# DebuggerMCU.net
KiCad netlist of a schematic drawn in Altium Designer
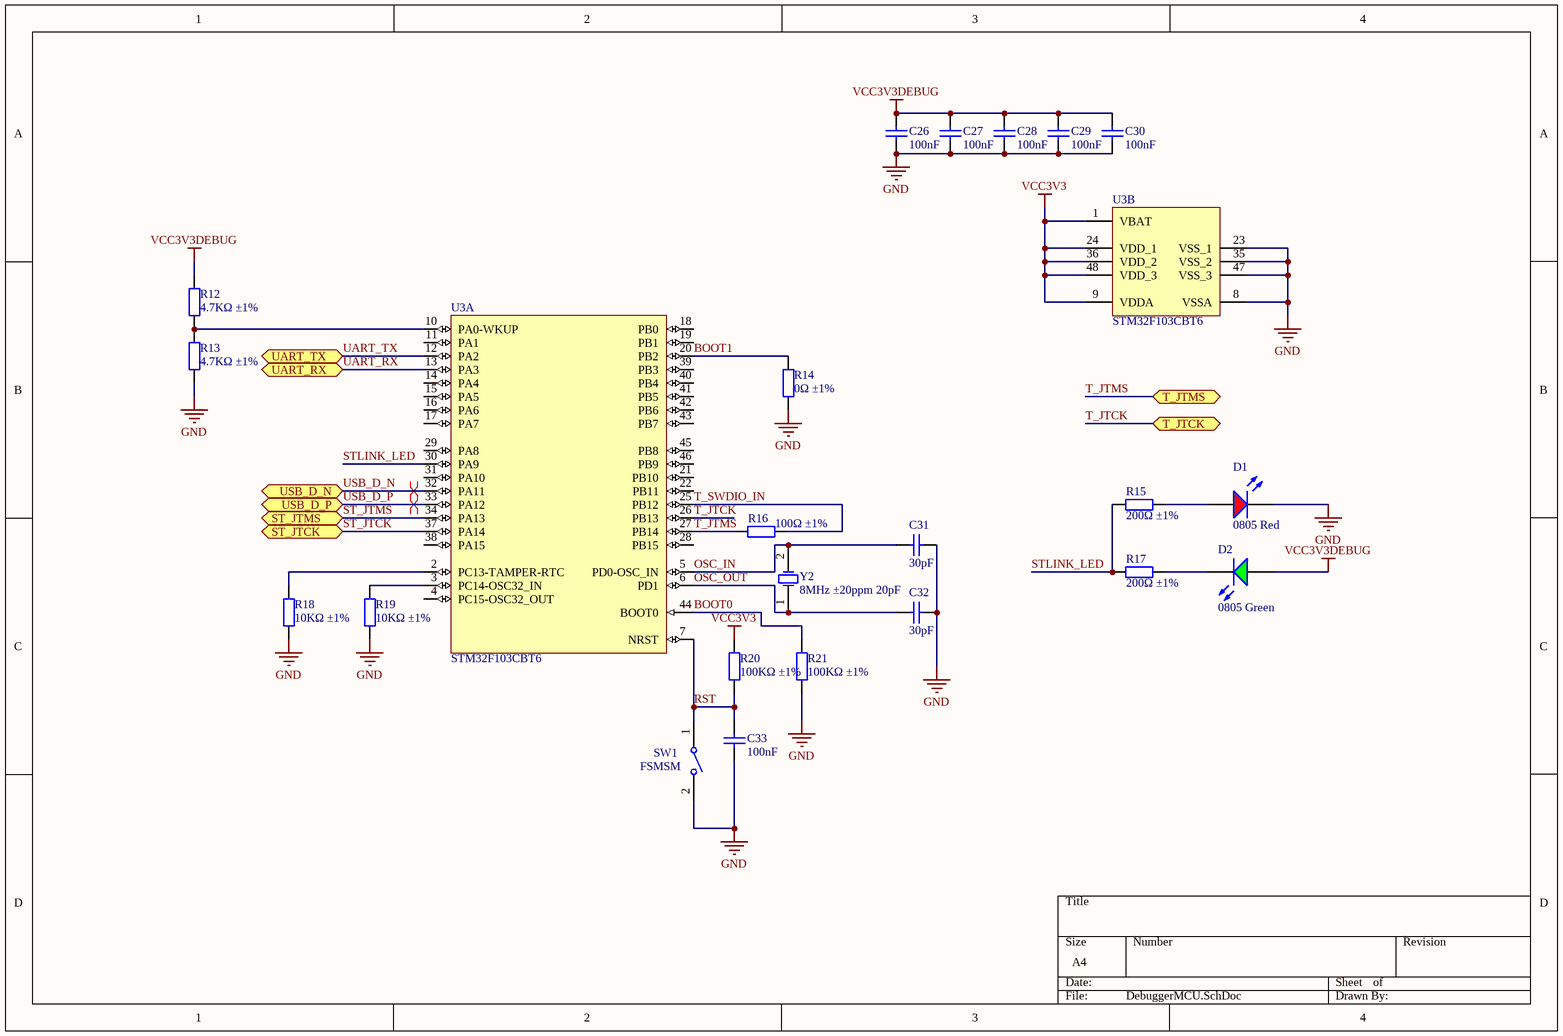
[diagram p0: DebuggerMCU.SchDoc]

(export (version "E")
  (design (tool "Eeschema 10.0.6"))
  (components
    (comp (ref "C26")
      (value "100nF")
      (footprint "0402_C")
      (description "Chip capacitors")
      (fields
        (field (name "MANUFACTURER") "Samsung Electro-Mechanics")
        (field (name "PARTNUMBER") "CL05B104KO5NNNC")
      )
      (libsource (lib "Miscellaneous Devices LC") (part "0402 100nF (104) 10% 16V"))
    )
    (comp (ref "C27")
      (value "100nF")
      (footprint "0402_C")
      (description "Chip capacitors")
      (fields
        (field (name "MANUFACTURER") "Samsung Electro-Mechanics")
        (field (name "PARTNUMBER") "CL05B104KO5NNNC")
      )
      (libsource (lib "Miscellaneous Devices LC") (part "0402 100nF (104) 10% 16V"))
    )
    (comp (ref "C28")
      (value "100nF")
      (footprint "0402_C")
      (description "Chip capacitors")
      (fields
        (field (name "MANUFACTURER") "Samsung Electro-Mechanics")
        (field (name "PARTNUMBER") "CL05B104KO5NNNC")
      )
      (libsource (lib "Miscellaneous Devices LC") (part "0402 100nF (104) 10% 16V"))
    )
    (comp (ref "C29")
      (value "100nF")
      (footprint "0402_C")
      (description "Chip capacitors")
      (fields
        (field (name "MANUFACTURER") "Samsung Electro-Mechanics")
        (field (name "PARTNUMBER") "CL05B104KO5NNNC")
      )
      (libsource (lib "Miscellaneous Devices LC") (part "0402 100nF (104) 10% 16V"))
    )
    (comp (ref "C30")
      (value "100nF")
      (footprint "0402_C")
      (description "Chip capacitors")
      (fields
        (field (name "MANUFACTURER") "Samsung Electro-Mechanics")
        (field (name "PARTNUMBER") "CL05B104KO5NNNC")
      )
      (libsource (lib "Miscellaneous Devices LC") (part "0402 100nF (104) 10% 16V"))
    )
    (comp (ref "C31")
      (value "30pF")
      (footprint "0402_C")
      (description "Chip capacitors")
      (fields
        (field (name "MANUFACTURER") "Guangdong Fenghua Advanced Tech")
        (field (name "PARTNUMBER") "0402CG300J500NT")
      )
      (libsource (lib "Miscellaneous Devices LC") (part "0402 30pF (300) 5% 50V"))
    )
    (comp (ref "C32")
      (value "30pF")
      (footprint "0402_C")
      (description "Chip capacitors")
      (fields
        (field (name "MANUFACTURER") "Guangdong Fenghua Advanced Tech")
        (field (name "PARTNUMBER") "0402CG300J500NT")
      )
      (libsource (lib "Miscellaneous Devices LC") (part "0402 30pF (300) 5% 50V"))
    )
    (comp (ref "C33")
      (value "100nF")
      (footprint "0402_C")
      (description "Chip capacitors")
      (fields
        (field (name "MANUFACTURER") "Samsung Electro-Mechanics")
        (field (name "PARTNUMBER") "CL05B104KO5NNNC")
      )
      (libsource (lib "Miscellaneous Devices LC") (part "0402 100nF (104) 10% 16V"))
    )
    (comp (ref "D1")
      (value "0805 Red")
      (footprint "0805_LED_S1")
      (description "LED")
      (libsource (lib "Miscellaneous Devices LC") (part "0805 LED Red"))
    )
    (comp (ref "D2")
      (value "0805 Green")
      (footprint "0805_LED_S1")
      (description "LED")
      (libsource (lib "Miscellaneous Devices LC") (part "0805 LED Green"))
    )
    (comp (ref "R12")
      (value "4.7KΩ ±1%")
      (footprint "0805_R")
      (description "Chip resistor")
      (fields (field (name "MANUFACTURER") "Uniroyal Elec") (field (name "POWER") "1/8W"))
      (libsource (lib "Miscellaneous Devices LC") (part "0805 4.7K (4701) 1%"))
    )
    (comp (ref "R13")
      (value "4.7KΩ ±1%")
      (footprint "0805_R")
      (description "Chip resistor")
      (fields (field (name "MANUFACTURER") "Uniroyal Elec") (field (name "POWER") "1/8W"))
      (libsource (lib "Miscellaneous Devices LC") (part "0805 4.7K (4701) 1%"))
    )
    (comp (ref "R14")
      (value "0Ω ±1%")
      (footprint "0402_R")
      (description "Chip resistor")
      (fields (field (name "POWER") "1/16W") (field (name "MANUFACTURER") "Uniroyal Elec"))
      (libsource (lib "Miscellaneous Devices LC") (part "0402 0R (0R0) 1%"))
    )
    (comp (ref "R15")
      (value "200Ω ±1%")
      (footprint "0402_R")
      (description "Chip resistor")
      (fields (field (name "MANUFACTURER") "Uniroyal Elec") (field (name "PARTNUMBER") "0402WGF2000TCE"))
      (libsource (lib "Miscellaneous Devices LC") (part "0402 200R (2000) 1%"))
    )
    (comp (ref "R16")
      (value "100Ω ±1%")
      (footprint "0402_R")
      (description "Chip resistor")
      (fields (field (name "MANUFACTURER") "Uniroyal Elec") (field (name "PARTNUMBER") "0402WGF1000TCE"))
      (libsource (lib "Miscellaneous Devices LC") (part "0402 100R (1000) 1%"))
    )
    (comp (ref "R17")
      (value "200Ω ±1%")
      (footprint "0402_R")
      (description "Chip resistor")
      (fields (field (name "MANUFACTURER") "Uniroyal Elec") (field (name "PARTNUMBER") "0402WGF2000TCE"))
      (libsource (lib "Miscellaneous Devices LC") (part "0402 200R (2000) 1%"))
    )
    (comp (ref "R18")
      (value "10KΩ ±1%")
      (footprint "0402_R")
      (description "Chip resistor")
      (fields (field (name "MANUFACTURER") "Uniroyal Elec") (field (name "PARTNUMBER") "0402WGF1002TCE"))
      (libsource (lib "Miscellaneous Devices LC") (part "0402 10K (1002) 1%"))
    )
    (comp (ref "R19")
      (value "10KΩ ±1%")
      (footprint "0402_R")
      (description "Chip resistor")
      (fields (field (name "MANUFACTURER") "Uniroyal Elec") (field (name "PARTNUMBER") "0402WGF1002TCE"))
      (libsource (lib "Miscellaneous Devices LC") (part "0402 10K (1002) 1%"))
    )
    (comp (ref "R20")
      (value "100KΩ ±1%")
      (footprint "0402_R")
      (description "Chip resistor")
      (fields (field (name "MANUFACTURER") "Uniroyal Elec") (field (name "PARTNUMBER") "0402WGF1003TCE"))
      (libsource (lib "Miscellaneous Devices LC") (part "0402 100K (1003) 1%"))
    )
    (comp (ref "R21")
      (value "100KΩ ±1%")
      (footprint "0402_R")
      (description "Chip resistor")
      (fields (field (name "MANUFACTURER") "Uniroyal Elec") (field (name "PARTNUMBER") "0402WGF1003TCE"))
      (libsource (lib "Miscellaneous Devices LC") (part "0402 100K (1003) 1%"))
    )
    (comp (ref "SW1")
      (value "FSMSM")
      (footprint "TECO-FSMSM-2_V")
      (description "FSMSM Push Button Switch, 50 mA, -35 to 85 degC, 2-Pin SMD, RoHS, Bulk")
      (fields (field (name "MANUFACTURER") "TE Connectivity"))
      (libsource (lib "Altium Content Vault") (part "SW-SPST-2_C"))
    )
    (comp (ref "U3")
      (value "STM32F103CBT6")
      (footprint "LQFP-48_7x7x05P")
      (description "ARM")
      (libsource (lib "Miscellaneous Devices LC") (part "STM32F103CBT6"))
    )
    (comp (ref "Y2")
      (value "8MHz ±20ppm 20pF")
      (footprint "SMD-5032_2P")
      (description "贴片晶振")
      (libsource (lib "Miscellaneous Devices LC") (part "SMD-5032_2P 8MHz 20ppm 20pF"))
    )
  )
  (nets
    (net (code "1") (name "/BOOT0") (class "Default")
      (node (ref "R21") (pin "2") (pinfunction "2_2") (pintype "passive"))
      (node (ref "U3") (pin "44") (pinfunction "BOOT0_44") (pintype "input"))
    )
    (net (code "2") (name "/BOOT1") (class "Default")
      (node (ref "R14") (pin "2") (pinfunction "2_2") (pintype "passive"))
      (node (ref "U3") (pin "20") (pinfunction "PB2_20") (pintype "bidirectional"))
    )
    (net (code "3") (name "/OSC_IN") (class "Default")
      (node (ref "C31") (pin "1") (pinfunction "1_1") (pintype "passive"))
      (node (ref "U3") (pin "5") (pinfunction "PD0-OSC_IN_5") (pintype "bidirectional"))
      (node (ref "Y2") (pin "2") (pinfunction "OSC2_2") (pintype "passive"))
    )
    (net (code "4") (name "/OSC_OUT") (class "Default")
      (node (ref "C32") (pin "1") (pinfunction "1_1") (pintype "passive"))
      (node (ref "U3") (pin "6") (pinfunction "PD1_6") (pintype "bidirectional"))
      (node (ref "Y2") (pin "1") (pinfunction "OSC1_1") (pintype "passive"))
    )
    (net (code "5") (name "/RST") (class "Default")
      (node (ref "C33") (pin "2") (pinfunction "2_2") (pintype "passive"))
      (node (ref "R20") (pin "1") (pinfunction "1_1") (pintype "passive"))
      (node (ref "SW1") (pin "1") (pinfunction "1_1") (pintype "passive"))
      (node (ref "U3") (pin "7") (pinfunction "NRST_7") (pintype "bidirectional"))
    )
    (net (code "6") (name "/STLINK_LED") (class "Default")
      (node (ref "R15") (pin "1") (pinfunction "1_1") (pintype "passive"))
      (node (ref "R17") (pin "1") (pinfunction "1_1") (pintype "passive"))
      (node (ref "U3") (pin "30") (pinfunction "PA9_30") (pintype "bidirectional"))
    )
    (net (code "7") (name "/ST_JTCK") (class "Default")
      (node (ref "U3") (pin "37") (pinfunction "PA14_37") (pintype "bidirectional"))
    )
    (net (code "8") (name "/ST_JTMS") (class "Default")
      (node (ref "U3") (pin "34") (pinfunction "PA13_34") (pintype "bidirectional"))
    )
    (net (code "9") (name "/T_JTCK") (class "Default")
      (node (ref "U3") (pin "26") (pinfunction "PB13_26") (pintype "bidirectional"))
    )
    (net (code "10") (name "/T_JTMS") (class "Default")
      (node (ref "R16") (pin "2") (pinfunction "2_2") (pintype "passive"))
      (node (ref "U3") (pin "27") (pinfunction "PB14_27") (pintype "bidirectional"))
    )
    (net (code "11") (name "/T_SWDIO_IN") (class "Default")
      (node (ref "R16") (pin "1") (pinfunction "1_1") (pintype "passive"))
      (node (ref "U3") (pin "25") (pinfunction "PB12_25") (pintype "bidirectional"))
    )
    (net (code "12") (name "/UART_RX") (class "Default")
      (node (ref "U3") (pin "13") (pinfunction "PA3_13") (pintype "bidirectional"))
    )
    (net (code "13") (name "/UART_TX") (class "Default")
      (node (ref "U3") (pin "12") (pinfunction "PA2_12") (pintype "bidirectional"))
    )
    (net (code "14") (name "/USB_D_N") (class "Default")
      (node (ref "U3") (pin "32") (pinfunction "PA11_32") (pintype "bidirectional"))
    )
    (net (code "15") (name "/USB_D_P") (class "Default")
      (node (ref "U3") (pin "33") (pinfunction "PA12_33") (pintype "bidirectional"))
    )
    (net (code "16") (name "GND") (class "Default")
      (node (ref "C26") (pin "1") (pinfunction "1_1") (pintype "passive"))
      (node (ref "C27") (pin "1") (pinfunction "1_1") (pintype "passive"))
      (node (ref "C28") (pin "1") (pinfunction "1_1") (pintype "passive"))
      (node (ref "C29") (pin "1") (pinfunction "1_1") (pintype "passive"))
      (node (ref "C30") (pin "1") (pinfunction "1_1") (pintype "passive"))
      (node (ref "C31") (pin "2") (pinfunction "2_2") (pintype "passive"))
      (node (ref "C32") (pin "2") (pinfunction "2_2") (pintype "passive"))
      (node (ref "C33") (pin "1") (pinfunction "1_1") (pintype "passive"))
      (node (ref "D1") (pin "K") (pinfunction "K_K") (pintype "passive"))
      (node (ref "R13") (pin "1") (pinfunction "1_1") (pintype "passive"))
      (node (ref "R14") (pin "1") (pinfunction "1_1") (pintype "passive"))
      (node (ref "R18") (pin "1") (pinfunction "1_1") (pintype "passive"))
      (node (ref "R19") (pin "1") (pinfunction "1_1") (pintype "passive"))
      (node (ref "R21") (pin "1") (pinfunction "1_1") (pintype "passive"))
      (node (ref "SW1") (pin "2") (pinfunction "2_2") (pintype "passive"))
      (node (ref "U3") (pin "23") (pinfunction "VSS_1_23") (pintype "power_in"))
      (node (ref "U3") (pin "35") (pinfunction "VSS_2_35") (pintype "power_in"))
      (node (ref "U3") (pin "47") (pinfunction "VSS_3_47") (pintype "power_in"))
      (node (ref "U3") (pin "8") (pinfunction "VSSA_8") (pintype "power_in"))
    )
    (net (code "17") (name "Net-(D1-PadA)") (class "Default")
      (node (ref "D1") (pin "A") (pinfunction "A_A") (pintype "passive"))
      (node (ref "R15") (pin "2") (pinfunction "2_2") (pintype "passive"))
    )
    (net (code "18") (name "Net-(D2-PadK)") (class "Default")
      (node (ref "D2") (pin "K") (pinfunction "K_K") (pintype "passive"))
      (node (ref "R17") (pin "2") (pinfunction "2_2") (pintype "passive"))
    )
    (net (code "19") (name "Net-(U3A-PA0-WKUP)") (class "Default")
      (node (ref "R12") (pin "1") (pinfunction "1_1") (pintype "passive"))
      (node (ref "R13") (pin "2") (pinfunction "2_2") (pintype "passive"))
      (node (ref "U3") (pin "10") (pinfunction "PA0-WKUP_10") (pintype "bidirectional"))
    )
    (net (code "20") (name "Net-(U3A-PC13-TAMPER-RTC)") (class "Default")
      (node (ref "R18") (pin "2") (pinfunction "2_2") (pintype "passive"))
      (node (ref "U3") (pin "2") (pinfunction "PC13-TAMPER-RTC_2") (pintype "bidirectional"))
    )
    (net (code "21") (name "Net-(U3A-PC14-OSC32_IN)") (class "Default")
      (node (ref "R19") (pin "2") (pinfunction "2_2") (pintype "passive"))
      (node (ref "U3") (pin "3") (pinfunction "PC14-OSC32_IN_3") (pintype "bidirectional"))
    )
    (net (code "22") (name "VCC3V3") (class "Default")
      (node (ref "R20") (pin "2") (pinfunction "2_2") (pintype "passive"))
      (node (ref "U3") (pin "1") (pinfunction "VBAT_1") (pintype "power_in"))
      (node (ref "U3") (pin "24") (pinfunction "VDD_1_24") (pintype "power_in"))
      (node (ref "U3") (pin "36") (pinfunction "VDD_2_36") (pintype "power_in"))
      (node (ref "U3") (pin "48") (pinfunction "VDD_3_48") (pintype "power_in"))
      (node (ref "U3") (pin "9") (pinfunction "VDDA_9") (pintype "power_in"))
    )
    (net (code "23") (name "VCC3V3DEBUG") (class "Default")
      (node (ref "C26") (pin "2") (pinfunction "2_2") (pintype "passive"))
      (node (ref "C27") (pin "2") (pinfunction "2_2") (pintype "passive"))
      (node (ref "C28") (pin "2") (pinfunction "2_2") (pintype "passive"))
      (node (ref "C29") (pin "2") (pinfunction "2_2") (pintype "passive"))
      (node (ref "C30") (pin "2") (pinfunction "2_2") (pintype "passive"))
      (node (ref "D2") (pin "A") (pinfunction "A_A") (pintype "passive"))
      (node (ref "R12") (pin "2") (pinfunction "2_2") (pintype "passive"))
    )
    (net (code "24") (name "unconnected-(U3A-PA1-Pad11)") (class "Default")
      (node (ref "U3") (pin "11") (pinfunction "PA1_11") (pintype "bidirectional"))
    )
    (net (code "25") (name "unconnected-(U3A-PA4-Pad14)") (class "Default")
      (node (ref "U3") (pin "14") (pinfunction "PA4_14") (pintype "bidirectional"))
    )
    (net (code "26") (name "unconnected-(U3A-PA5-Pad15)") (class "Default")
      (node (ref "U3") (pin "15") (pinfunction "PA5_15") (pintype "bidirectional"))
    )
    (net (code "27") (name "unconnected-(U3A-PA6-Pad16)") (class "Default")
      (node (ref "U3") (pin "16") (pinfunction "PA6_16") (pintype "bidirectional"))
    )
    (net (code "28") (name "unconnected-(U3A-PA7-Pad17)") (class "Default")
      (node (ref "U3") (pin "17") (pinfunction "PA7_17") (pintype "bidirectional"))
    )
    (net (code "29") (name "unconnected-(U3A-PA8-Pad29)") (class "Default")
      (node (ref "U3") (pin "29") (pinfunction "PA8_29") (pintype "bidirectional"))
    )
    (net (code "30") (name "unconnected-(U3A-PA10-Pad31)") (class "Default")
      (node (ref "U3") (pin "31") (pinfunction "PA10_31") (pintype "bidirectional"))
    )
    (net (code "31") (name "unconnected-(U3A-PA15-Pad38)") (class "Default")
      (node (ref "U3") (pin "38") (pinfunction "PA15_38") (pintype "bidirectional"))
    )
    (net (code "32") (name "unconnected-(U3A-PB0-Pad18)") (class "Default")
      (node (ref "U3") (pin "18") (pinfunction "PB0_18") (pintype "bidirectional"))
    )
    (net (code "33") (name "unconnected-(U3A-PB1-Pad19)") (class "Default")
      (node (ref "U3") (pin "19") (pinfunction "PB1_19") (pintype "bidirectional"))
    )
    (net (code "34") (name "unconnected-(U3A-PB3-Pad39)") (class "Default")
      (node (ref "U3") (pin "39") (pinfunction "PB3_39") (pintype "bidirectional"))
    )
    (net (code "35") (name "unconnected-(U3A-PB4-Pad40)") (class "Default")
      (node (ref "U3") (pin "40") (pinfunction "PB4_40") (pintype "bidirectional"))
    )
    (net (code "36") (name "unconnected-(U3A-PB5-Pad41)") (class "Default")
      (node (ref "U3") (pin "41") (pinfunction "PB5_41") (pintype "bidirectional"))
    )
    (net (code "37") (name "unconnected-(U3A-PB6-Pad42)") (class "Default")
      (node (ref "U3") (pin "42") (pinfunction "PB6_42") (pintype "bidirectional"))
    )
    (net (code "38") (name "unconnected-(U3A-PB7-Pad43)") (class "Default")
      (node (ref "U3") (pin "43") (pinfunction "PB7_43") (pintype "bidirectional"))
    )
    (net (code "39") (name "unconnected-(U3A-PB8-Pad45)") (class "Default")
      (node (ref "U3") (pin "45") (pinfunction "PB8_45") (pintype "bidirectional"))
    )
    (net (code "40") (name "unconnected-(U3A-PB9-Pad46)") (class "Default")
      (node (ref "U3") (pin "46") (pinfunction "PB9_46") (pintype "bidirectional"))
    )
    (net (code "41") (name "unconnected-(U3A-PB10-Pad21)") (class "Default")
      (node (ref "U3") (pin "21") (pinfunction "PB10_21") (pintype "bidirectional"))
    )
    (net (code "42") (name "unconnected-(U3A-PB11-Pad22)") (class "Default")
      (node (ref "U3") (pin "22") (pinfunction "PB11_22") (pintype "bidirectional"))
    )
    (net (code "43") (name "unconnected-(U3A-PB15-Pad28)") (class "Default")
      (node (ref "U3") (pin "28") (pinfunction "PB15_28") (pintype "bidirectional"))
    )
    (net (code "44") (name "unconnected-(U3A-PC15-OSC32_OUT-Pad4)") (class "Default")
      (node (ref "U3") (pin "4") (pinfunction "PC15-OSC32_OUT_4") (pintype "bidirectional"))
    )
  )
)
